# output1.net
KiCad netlist of a schematic drawn in Altium Designer
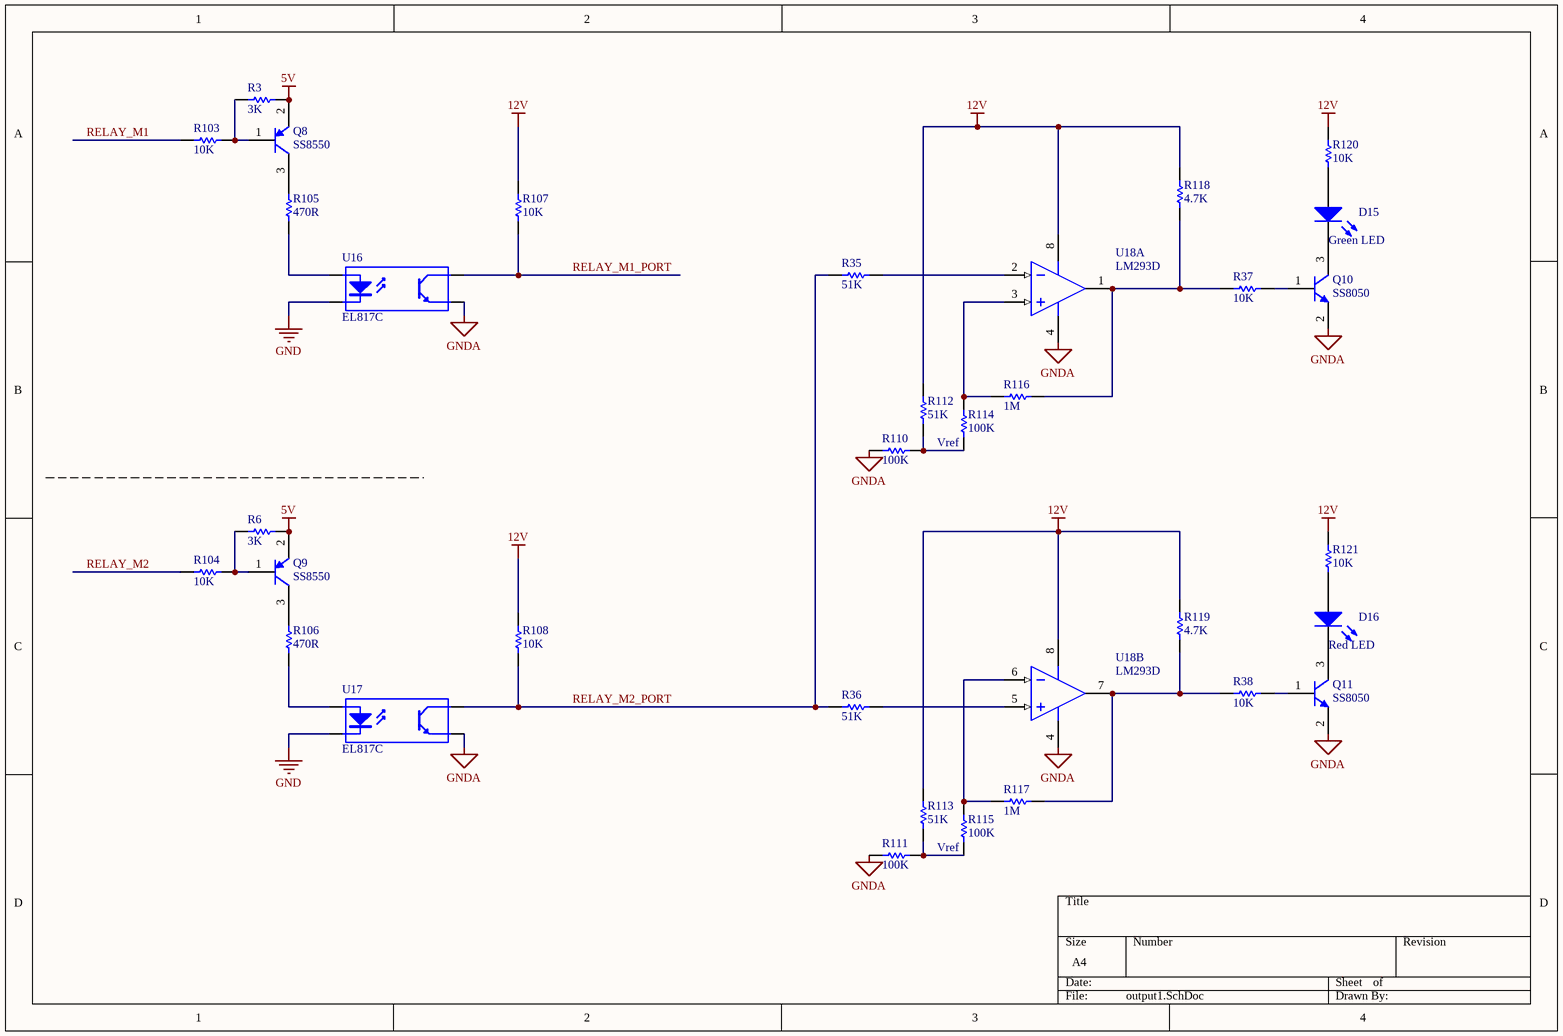
[diagram p0: output1.SchDoc]

(export (version "E")
  (design (tool "Eeschema 10.0.6"))
  (components
    (comp (ref "D15")
      (value "Green LED")
      (footprint "LED254A")
      (description "Green LED ,SIP, Dia =3mm")
      (fields (field (name "PUBLISHER") "Altium Limited"))
      (libsource (lib "Miscellaneous Devices") (part "LED1"))
    )
    (comp (ref "D16")
      (value "Red LED")
      (footprint "LED254A")
      (description "Red LED ,SIP, Dia =3mm")
      (fields (field (name "PUBLISHER") "Altium Limited"))
      (libsource (lib "Miscellaneous Devices") (part "LED1"))
    )
    (comp (ref "Q8")
      (value "SS8550")
      (footprint "SOT-23_N")
      (description "PNP General Purpose Amplifier")
      (fields (field (name "PUBLISHER") "Altium Limited"))
      (libsource (lib "Miscellaneous Devices") (part "2N3906"))
    )
    (comp (ref "Q9")
      (value "SS8550")
      (footprint "SOT-23_N")
      (description "PNP General Purpose Amplifier")
      (fields (field (name "PUBLISHER") "Altium Limited"))
      (libsource (lib "Miscellaneous Devices") (part "2N3906"))
    )
    (comp (ref "Q10")
      (value "SS8050")
      (footprint "SOT-23_N")
      (description "NPN BISS Transistor")
      (fields (field (name "PUBLISHER") "Altium Limited"))
      (libsource (lib "Philips Discrete BJT - Low Power") (part "PMMT491A"))
    )
    (comp (ref "Q11")
      (value "SS8050")
      (footprint "SOT-23_N")
      (description "NPN BISS Transistor")
      (fields (field (name "PUBLISHER") "Altium Limited"))
      (libsource (lib "Philips Discrete BJT - Low Power") (part "PMMT491A"))
    )
    (comp (ref "R3")
      (value "3K")
      (footprint "RESC2012M")
      (description "Resistor")
      (fields (field (name "PUBLISHER") "Altium Limited"))
      (libsource (lib "Miscellaneous Devices") (part "Res1"))
    )
    (comp (ref "R6")
      (value "3K")
      (footprint "RESC2012M")
      (description "Resistor")
      (fields (field (name "PUBLISHER") "Altium Limited"))
      (libsource (lib "Miscellaneous Devices") (part "Res1"))
    )
    (comp (ref "R35")
      (value "51K")
      (footprint "RESC2012M")
      (description "Resistor")
      (fields (field (name "PUBLISHER") "Altium Limited"))
      (libsource (lib "Miscellaneous Devices") (part "Res1"))
    )
    (comp (ref "R36")
      (value "51K")
      (footprint "RESC2012M")
      (description "Resistor")
      (fields (field (name "PUBLISHER") "Altium Limited"))
      (libsource (lib "Miscellaneous Devices") (part "Res1"))
    )
    (comp (ref "R37")
      (value "10K")
      (footprint "RESC2012M")
      (description "Resistor")
      (fields (field (name "PUBLISHER") "Altium Limited"))
      (libsource (lib "Miscellaneous Devices") (part "Res1"))
    )
    (comp (ref "R38")
      (value "10K")
      (footprint "RESC2012M")
      (description "Resistor")
      (fields (field (name "PUBLISHER") "Altium Limited"))
      (libsource (lib "Miscellaneous Devices") (part "Res1"))
    )
    (comp (ref "R103")
      (value "10K")
      (footprint "RESC2012M")
      (description "Resistor")
      (fields (field (name "PUBLISHER") "Altium Limited"))
      (libsource (lib "Miscellaneous Devices") (part "Res1"))
    )
    (comp (ref "R104")
      (value "10K")
      (footprint "RESC2012M")
      (description "Resistor")
      (fields (field (name "PUBLISHER") "Altium Limited"))
      (libsource (lib "Miscellaneous Devices") (part "Res1"))
    )
    (comp (ref "R105")
      (value "470R")
      (footprint "RESC2012M")
      (description "Resistor")
      (fields (field (name "PUBLISHER") "Altium Limited"))
      (libsource (lib "Miscellaneous Devices") (part "Res1"))
    )
    (comp (ref "R106")
      (value "470R")
      (footprint "RESC2012M")
      (description "Resistor")
      (fields (field (name "PUBLISHER") "Altium Limited"))
      (libsource (lib "Miscellaneous Devices") (part "Res1"))
    )
    (comp (ref "R107")
      (value "10K")
      (footprint "RESC2012M")
      (description "Resistor")
      (fields (field (name "PUBLISHER") "Altium Limited"))
      (libsource (lib "Miscellaneous Devices") (part "Res1"))
    )
    (comp (ref "R108")
      (value "10K")
      (footprint "RESC2012M")
      (description "Resistor")
      (fields (field (name "PUBLISHER") "Altium Limited"))
      (libsource (lib "Miscellaneous Devices") (part "Res1"))
    )
    (comp (ref "R110")
      (value "100K")
      (footprint "RESC2012M")
      (description "Resistor")
      (fields (field (name "PUBLISHER") "Altium Limited"))
      (libsource (lib "Miscellaneous Devices") (part "Res1"))
    )
    (comp (ref "R111")
      (value "100K")
      (footprint "RESC2012M")
      (description "Resistor")
      (fields (field (name "PUBLISHER") "Altium Limited"))
      (libsource (lib "Miscellaneous Devices") (part "Res1"))
    )
    (comp (ref "R112")
      (value "51K")
      (footprint "RESC2012M")
      (description "Resistor")
      (fields (field (name "PUBLISHER") "Altium Limited"))
      (libsource (lib "Miscellaneous Devices") (part "Res1"))
    )
    (comp (ref "R113")
      (value "51K")
      (footprint "RESC2012M")
      (description "Resistor")
      (fields (field (name "PUBLISHER") "Altium Limited"))
      (libsource (lib "Miscellaneous Devices") (part "Res1"))
    )
    (comp (ref "R114")
      (value "100K")
      (footprint "RESC2012M")
      (description "Resistor")
      (fields (field (name "PUBLISHER") "Altium Limited"))
      (libsource (lib "Miscellaneous Devices") (part "Res1"))
    )
    (comp (ref "R115")
      (value "100K")
      (footprint "RESC2012M")
      (description "Resistor")
      (fields (field (name "PUBLISHER") "Altium Limited"))
      (libsource (lib "Miscellaneous Devices") (part "Res1"))
    )
    (comp (ref "R116")
      (value "1M")
      (footprint "RESC2012M")
      (description "Resistor")
      (fields (field (name "PUBLISHER") "Altium Limited"))
      (libsource (lib "Miscellaneous Devices") (part "Res1"))
    )
    (comp (ref "R117")
      (value "1M")
      (footprint "RESC2012M")
      (description "Resistor")
      (fields (field (name "PUBLISHER") "Altium Limited"))
      (libsource (lib "Miscellaneous Devices") (part "Res1"))
    )
    (comp (ref "R118")
      (value "4.7K")
      (footprint "RESC2012M")
      (description "Resistor")
      (fields (field (name "PUBLISHER") "Altium Limited"))
      (libsource (lib "Miscellaneous Devices") (part "Res1"))
    )
    (comp (ref "R119")
      (value "4.7K")
      (footprint "RESC2012M")
      (description "Resistor")
      (fields (field (name "PUBLISHER") "Altium Limited"))
      (libsource (lib "Miscellaneous Devices") (part "Res1"))
    )
    (comp (ref "R120")
      (value "10K")
      (footprint "RESC2012M")
      (description "Resistor")
      (fields (field (name "PUBLISHER") "Altium Limited"))
      (libsource (lib "Miscellaneous Devices") (part "Res1"))
    )
    (comp (ref "R121")
      (value "10K")
      (footprint "RESC2012M")
      (description "Resistor")
      (fields (field (name "PUBLISHER") "Altium Limited"))
      (libsource (lib "Miscellaneous Devices") (part "Res1"))
    )
    (comp (ref "U16")
      (value "EL817C")
      (footprint "SO-4LA")
      (description "4-Pin Phototransistor Optocoupler")
      (fields (field (name "PUBLISHER") "Altium Limited"))
      (libsource (lib "Miscellaneous Devices") (part "Optoisolator1"))
    )
    (comp (ref "U17")
      (value "EL817C")
      (footprint "SO-4LA")
      (description "4-Pin Phototransistor Optocoupler")
      (fields (field (name "PUBLISHER") "Altium Limited"))
      (libsource (lib "Miscellaneous Devices") (part "Optoisolator1"))
    )
    (comp (ref "U18")
      (value "LM293D")
      (footprint "SO8_N")
      (description "Low-Power Dual Voltage Comparator")
      (fields (field (name "PUBLISHER") "Altium Limited"))
      (libsource (lib "ST Analog Comparator") (part "LM293D"))
    )
  )
  (nets
    (net (code "1") (name "/RELAY_M1") (class "Default")
      (node (ref "R103") (pin "1") (pinfunction "1_1") (pintype "passive"))
    )
    (net (code "2") (name "/RELAY_M1_PORT") (class "Default")
      (node (ref "R107") (pin "1") (pinfunction "1_1") (pintype "passive"))
      (node (ref "U16") (pin "4") (pinfunction "C_4") (pintype "passive"))
    )
    (net (code "3") (name "/RELAY_M2") (class "Default")
      (node (ref "R104") (pin "1") (pinfunction "1_1") (pintype "passive"))
    )
    (net (code "4") (name "/RELAY_M2_PORT") (class "Default")
      (node (ref "R108") (pin "1") (pinfunction "1_1") (pintype "passive"))
      (node (ref "R35") (pin "1") (pinfunction "1_1") (pintype "passive"))
      (node (ref "R36") (pin "2") (pinfunction "2_2") (pintype "passive"))
      (node (ref "U17") (pin "4") (pinfunction "C_4") (pintype "passive"))
    )
    (net (code "5") (name "5V") (class "Default")
      (node (ref "Q8") (pin "2") (pinfunction "E_2") (pintype "passive"))
      (node (ref "Q9") (pin "2") (pinfunction "E_2") (pintype "passive"))
      (node (ref "R3") (pin "1") (pinfunction "1_1") (pintype "passive"))
      (node (ref "R6") (pin "1") (pinfunction "1_1") (pintype "passive"))
    )
    (net (code "6") (name "12V") (class "Default")
      (node (ref "R107") (pin "2") (pinfunction "2_2") (pintype "passive"))
      (node (ref "R108") (pin "2") (pinfunction "2_2") (pintype "passive"))
      (node (ref "R112") (pin "2") (pinfunction "2_2") (pintype "passive"))
      (node (ref "R113") (pin "2") (pinfunction "2_2") (pintype "passive"))
      (node (ref "R118") (pin "1") (pinfunction "1_1") (pintype "passive"))
      (node (ref "R119") (pin "1") (pinfunction "1_1") (pintype "passive"))
      (node (ref "R120") (pin "2") (pinfunction "2_2") (pintype "passive"))
      (node (ref "R121") (pin "2") (pinfunction "2_2") (pintype "passive"))
      (node (ref "U18") (pin "8") (pinfunction "V+_8") (pintype "power_in"))
    )
    (net (code "7") (name "GND") (class "Default")
      (node (ref "U16") (pin "2") (pinfunction "K_2") (pintype "passive"))
      (node (ref "U17") (pin "2") (pinfunction "K_2") (pintype "passive"))
    )
    (net (code "8") (name "GNDA") (class "Default")
      (node (ref "Q10") (pin "2") (pinfunction "E_2") (pintype "passive"))
      (node (ref "Q11") (pin "2") (pinfunction "E_2") (pintype "passive"))
      (node (ref "R110") (pin "1") (pinfunction "1_1") (pintype "passive"))
      (node (ref "R111") (pin "1") (pinfunction "1_1") (pintype "passive"))
      (node (ref "U16") (pin "3") (pinfunction "E_3") (pintype "passive"))
      (node (ref "U17") (pin "3") (pinfunction "E_3") (pintype "passive"))
      (node (ref "U18") (pin "4") (pinfunction "V-_4") (pintype "power_in"))
    )
    (net (code "9") (name "Net-(D15-A)") (class "Default")
      (node (ref "D15") (pin "1") (pinfunction "A_1") (pintype "passive"))
      (node (ref "R120") (pin "1") (pinfunction "1_1") (pintype "passive"))
    )
    (net (code "10") (name "Net-(D15-K)") (class "Default")
      (node (ref "D15") (pin "2") (pinfunction "K_2") (pintype "passive"))
      (node (ref "Q10") (pin "3") (pinfunction "C_3") (pintype "passive"))
    )
    (net (code "11") (name "Net-(D16-A)") (class "Default")
      (node (ref "D16") (pin "1") (pinfunction "A_1") (pintype "passive"))
      (node (ref "R121") (pin "1") (pinfunction "1_1") (pintype "passive"))
    )
    (net (code "12") (name "Net-(D16-K)") (class "Default")
      (node (ref "D16") (pin "2") (pinfunction "K_2") (pintype "passive"))
      (node (ref "Q11") (pin "3") (pinfunction "C_3") (pintype "passive"))
    )
    (net (code "13") (name "Net-(Q8-B)") (class "Default")
      (node (ref "Q8") (pin "1") (pinfunction "B_1") (pintype "passive"))
      (node (ref "R103") (pin "2") (pinfunction "2_2") (pintype "passive"))
      (node (ref "R3") (pin "2") (pinfunction "2_2") (pintype "passive"))
    )
    (net (code "14") (name "Net-(Q8-C)") (class "Default")
      (node (ref "Q8") (pin "3") (pinfunction "C_3") (pintype "passive"))
      (node (ref "R105") (pin "1") (pinfunction "1_1") (pintype "passive"))
    )
    (net (code "15") (name "Net-(Q9-B)") (class "Default")
      (node (ref "Q9") (pin "1") (pinfunction "B_1") (pintype "passive"))
      (node (ref "R104") (pin "2") (pinfunction "2_2") (pintype "passive"))
      (node (ref "R6") (pin "2") (pinfunction "2_2") (pintype "passive"))
    )
    (net (code "16") (name "Net-(Q9-C)") (class "Default")
      (node (ref "Q9") (pin "3") (pinfunction "C_3") (pintype "passive"))
      (node (ref "R106") (pin "1") (pinfunction "1_1") (pintype "passive"))
    )
    (net (code "17") (name "Net-(Q10-B)") (class "Default")
      (node (ref "Q10") (pin "1") (pinfunction "B_1") (pintype "passive"))
      (node (ref "R37") (pin "1") (pinfunction "1_1") (pintype "passive"))
    )
    (net (code "18") (name "Net-(Q11-B)") (class "Default")
      (node (ref "Q11") (pin "1") (pinfunction "B_1") (pintype "passive"))
      (node (ref "R38") (pin "2") (pinfunction "2_2") (pintype "passive"))
    )
    (net (code "19") (name "Net-(R110-Pad2)") (class "Default")
      (node (ref "R110") (pin "2") (pinfunction "2_2") (pintype "passive"))
      (node (ref "R112") (pin "1") (pinfunction "1_1") (pintype "passive"))
      (node (ref "R114") (pin "2") (pinfunction "2_2") (pintype "passive"))
    )
    (net (code "20") (name "Net-(R111-Pad2)") (class "Default")
      (node (ref "R111") (pin "2") (pinfunction "2_2") (pintype "passive"))
      (node (ref "R113") (pin "1") (pinfunction "1_1") (pintype "passive"))
      (node (ref "R115") (pin "2") (pinfunction "2_2") (pintype "passive"))
    )
    (net (code "21") (name "Net-(U16-A)") (class "Default")
      (node (ref "R105") (pin "2") (pinfunction "2_2") (pintype "passive"))
      (node (ref "U16") (pin "1") (pinfunction "A_1") (pintype "passive"))
    )
    (net (code "22") (name "Net-(U17-A)") (class "Default")
      (node (ref "R106") (pin "2") (pinfunction "2_2") (pintype "passive"))
      (node (ref "U17") (pin "1") (pinfunction "A_1") (pintype "passive"))
    )
    (net (code "23") (name "Net-(U18A-IN+)") (class "Default")
      (node (ref "R114") (pin "1") (pinfunction "1_1") (pintype "passive"))
      (node (ref "R116") (pin "1") (pinfunction "1_1") (pintype "passive"))
      (node (ref "U18") (pin "3") (pinfunction "IN+_3") (pintype "input"))
    )
    (net (code "24") (name "Net-(U18A-IN-)") (class "Default")
      (node (ref "R35") (pin "2") (pinfunction "2_2") (pintype "passive"))
      (node (ref "U18") (pin "2") (pinfunction "IN-_2") (pintype "input"))
    )
    (net (code "25") (name "Net-(U18A-OUT)") (class "Default")
      (node (ref "R116") (pin "2") (pinfunction "2_2") (pintype "passive"))
      (node (ref "R118") (pin "2") (pinfunction "2_2") (pintype "passive"))
      (node (ref "R37") (pin "2") (pinfunction "2_2") (pintype "passive"))
      (node (ref "U18") (pin "1") (pinfunction "OUT_1") (pintype "open_collector"))
    )
    (net (code "26") (name "Net-(U18B-IN+)") (class "Default")
      (node (ref "R36") (pin "1") (pinfunction "1_1") (pintype "passive"))
      (node (ref "U18") (pin "5") (pinfunction "IN+_5") (pintype "input"))
    )
    (net (code "27") (name "Net-(U18B-IN-)") (class "Default")
      (node (ref "R115") (pin "1") (pinfunction "1_1") (pintype "passive"))
      (node (ref "R117") (pin "1") (pinfunction "1_1") (pintype "passive"))
      (node (ref "U18") (pin "6") (pinfunction "IN-_6") (pintype "input"))
    )
    (net (code "28") (name "Net-(U18B-OUT)") (class "Default")
      (node (ref "R117") (pin "2") (pinfunction "2_2") (pintype "passive"))
      (node (ref "R119") (pin "2") (pinfunction "2_2") (pintype "passive"))
      (node (ref "R38") (pin "1") (pinfunction "1_1") (pintype "passive"))
      (node (ref "U18") (pin "7") (pinfunction "OUT_7") (pintype "open_collector"))
    )
  )
)
